# Measurements.net
KiCad netlist of a schematic drawn in Altium Designer
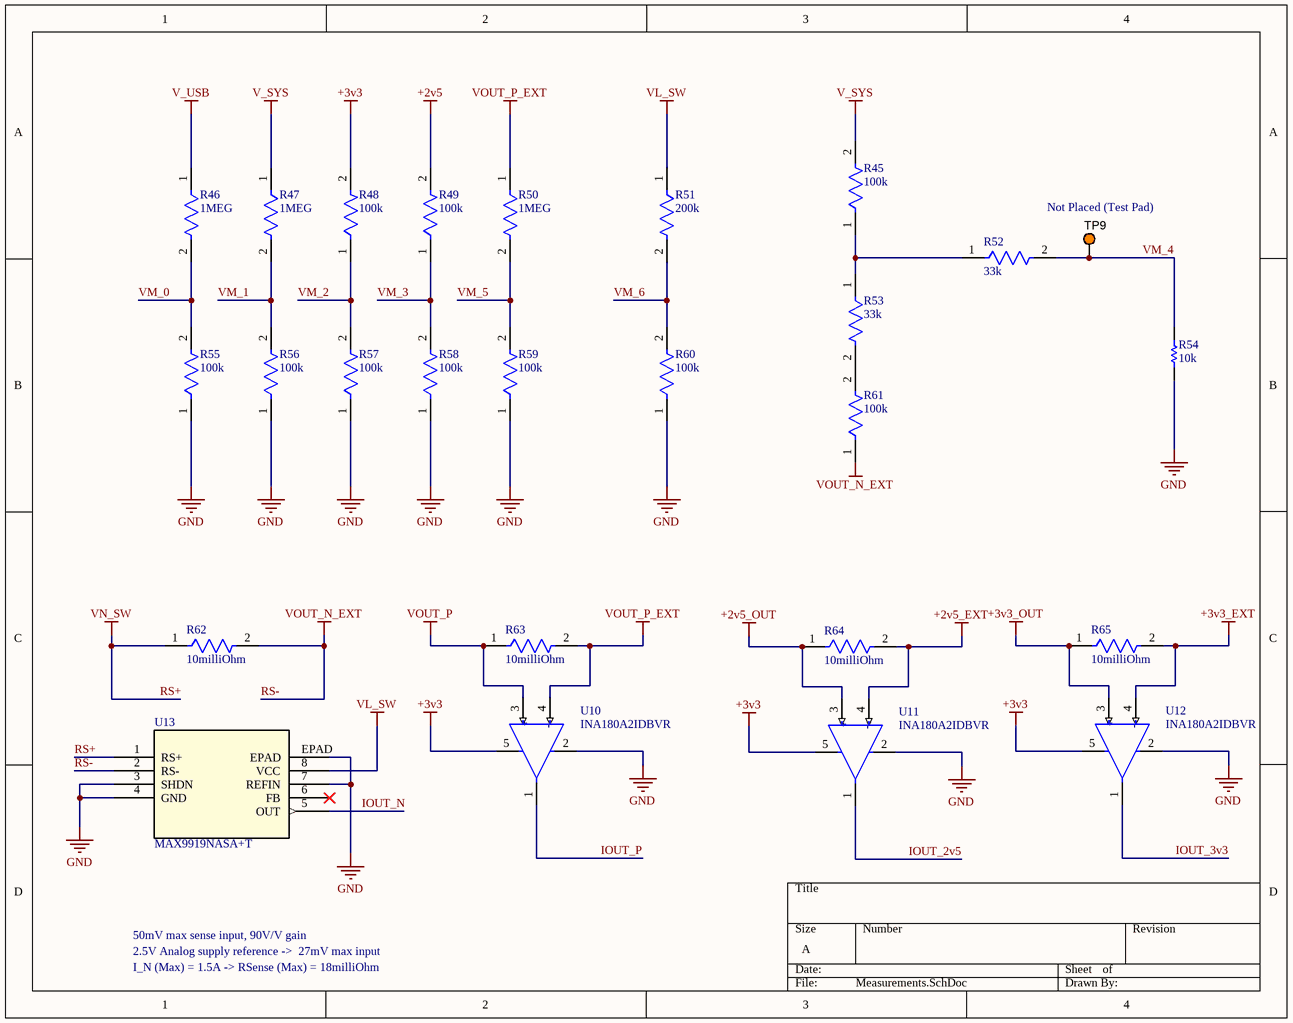
[diagram p0: Measurements.SchDoc]

(export (version "E")
  (design (tool "Eeschema 10.0.6"))
  (components
    (comp (ref "R45")
      (value "100k")
      (footprint "FP-AC0603-IPC_A")
      (description "RES 100kΩ 1.00% 0.2W 0603")
      (libsource (lib "Altium Content Vault") (part "1029c3af85768c4190bb7ad29bc67b5"))
    )
    (comp (ref "R46")
      (value "1MEG")
      (footprint "FP-AC0603-IPC_A")
      (description "RES 1MΩ 1.00% 0.1W 0603")
      (fields (field (name "TOLERANCE") "1%"))
      (libsource (lib "Altium Content Vault") (part "1029c3af85768c4190bb7ad29bc67b5"))
    )
    (comp (ref "R47")
      (value "1MEG")
      (footprint "FP-AC0603-IPC_A")
      (description "RES 1MΩ 1.00% 0.1W 0603")
      (fields (field (name "TOLERANCE") "1%"))
      (libsource (lib "Altium Content Vault") (part "1029c3af85768c4190bb7ad29bc67b5"))
    )
    (comp (ref "R48")
      (value "100k")
      (footprint "FP-AC0603-IPC_A")
      (description "RES 100kΩ 1.00% 0.2W 0603")
      (libsource (lib "Altium Content Vault") (part "1029c3af85768c4190bb7ad29bc67b5"))
    )
    (comp (ref "R49")
      (value "100k")
      (footprint "FP-AC0603-IPC_A")
      (description "RES 100kΩ 1.00% 0.2W 0603")
      (libsource (lib "Altium Content Vault") (part "1029c3af85768c4190bb7ad29bc67b5"))
    )
    (comp (ref "R50")
      (value "1MEG")
      (footprint "FP-AC0603-IPC_A")
      (description "RES 1MΩ 1.00% 0.1W 0603")
      (fields (field (name "TOLERANCE") "1%"))
      (libsource (lib "Altium Content Vault") (part "1029c3af85768c4190bb7ad29bc67b5"))
    )
    (comp (ref "R51")
      (value "200k")
      (footprint "FP-RMCF0603-IPC_A")
      (description "200kΩ ±1% 0.1W 0603 Thick Film Chip Resistor AEC-Q200 compliant")
      (fields (field (name "TOLERANCE") "1%"))
      (libsource (lib "Altium Content Vault") (part "1029c3af85768c4190bb7ad29bc67b5"))
    )
    (comp (ref "R52")
      (value "33k")
      (footprint "FP-CRGCQ0603-IPC_C")
      (description "CRGCQ0603 33KΩ 5% ±100ppm/°C 75V")
      (fields
        (field (name "MANUFACTURER PART NUMBER") "CRGCQ0603J33K")
        (field (name "OCTOPART") "https://octopart.com/crgcq0603j33k-te+connectivity-91018119")
      )
      (libsource (lib "Altium Content Vault") (part "1029c3af85768c4190bb7ad29bc67b5"))
    )
    (comp (ref "R53")
      (value "33k")
      (footprint "FP-CRGCQ0603-IPC_C")
      (description "CRGCQ0603 33KΩ 5% ±100ppm/°C 75V")
      (fields
        (field (name "MANUFACTURER PART NUMBER") "CRGCQ0603J33K")
        (field (name "OCTOPART") "https://octopart.com/crgcq0603j33k-te+connectivity-91018119")
      )
      (libsource (lib "Altium Content Vault") (part "1029c3af85768c4190bb7ad29bc67b5"))
    )
    (comp (ref "R54")
      (value "10k")
      (footprint "RESC1608X55X30NL15T15")
      (fields (field (name "PART NUMBER") "ERJ-3EKF1502V") (field (name "MANUFACTURER") "Panasonic"))
      (libsource (lib "Altium Content Vault") (part "RES"))
    )
    (comp (ref "R55")
      (value "100k")
      (footprint "FP-AC0603-IPC_A")
      (description "RES 100kΩ 1.00% 0.2W 0603")
      (libsource (lib "Altium Content Vault") (part "1029c3af85768c4190bb7ad29bc67b5"))
    )
    (comp (ref "R56")
      (value "100k")
      (footprint "FP-AC0603-IPC_A")
      (description "RES 100kΩ 1.00% 0.2W 0603")
      (libsource (lib "Altium Content Vault") (part "1029c3af85768c4190bb7ad29bc67b5"))
    )
    (comp (ref "R57")
      (value "100k")
      (footprint "FP-AC0603-IPC_A")
      (description "RES 100kΩ 1.00% 0.2W 0603")
      (libsource (lib "Altium Content Vault") (part "1029c3af85768c4190bb7ad29bc67b5"))
    )
    (comp (ref "R58")
      (value "100k")
      (footprint "FP-AC0603-IPC_A")
      (description "RES 100kΩ 1.00% 0.2W 0603")
      (libsource (lib "Altium Content Vault") (part "1029c3af85768c4190bb7ad29bc67b5"))
    )
    (comp (ref "R59")
      (value "100k")
      (footprint "FP-AC0603-IPC_A")
      (description "RES 100kΩ 1.00% 0.2W 0603")
      (libsource (lib "Altium Content Vault") (part "1029c3af85768c4190bb7ad29bc67b5"))
    )
    (comp (ref "R60")
      (value "100k")
      (footprint "FP-AC0603-IPC_A")
      (description "RES 100kΩ 1.00% 0.2W 0603")
      (libsource (lib "Altium Content Vault") (part "1029c3af85768c4190bb7ad29bc67b5"))
    )
    (comp (ref "R61")
      (value "100k")
      (footprint "FP-AC0603-IPC_A")
      (description "RES 100kΩ 1.00% 0.2W 0603")
      (libsource (lib "Altium Content Vault") (part "1029c3af85768c4190bb7ad29bc67b5"))
    )
    (comp (ref "R62")
      (value "10milliOhm")
      (footprint "FP-CSRF0603-high-IPC_A")
      (description "RES 0.01 OHM 1% 1/4W 0603")
      (fields (field (name "TOLERANCE") "1%"))
      (libsource (lib "Altium Content Vault") (part "1029c3af85768c4190bb7ad29bc67b5"))
    )
    (comp (ref "R63")
      (value "10milliOhm")
      (footprint "FP-CSRF0603-high-IPC_A")
      (description "RES 0.01 OHM 1% 1/4W 0603")
      (fields (field (name "TOLERANCE") "1%"))
      (libsource (lib "Altium Content Vault") (part "1029c3af85768c4190bb7ad29bc67b5"))
    )
    (comp (ref "R64")
      (value "10milliOhm")
      (footprint "FP-CSRF0603-high-IPC_A")
      (description "RES 0.01 OHM 1% 1/4W 0603")
      (fields (field (name "TOLERANCE") "1%"))
      (libsource (lib "Altium Content Vault") (part "1029c3af85768c4190bb7ad29bc67b5"))
    )
    (comp (ref "R65")
      (value "10milliOhm")
      (footprint "FP-CSRF0603-high-IPC_A")
      (description "RES 0.01 OHM 1% 1/4W 0603")
      (fields (field (name "TOLERANCE") "1%"))
      (libsource (lib "Altium Content Vault") (part "1029c3af85768c4190bb7ad29bc67b5"))
    )
    (comp (ref "TP9")
      (value "5003")
      (footprint "KSTN-5003")
      (description "Test Point, Orange, 1-Pin THD, RoHS")
      (libsource (lib "Altium Content Vault") (part "TESTPOINT_ORANGE"))
    )
    (comp (ref "U10")
      (value "INA180A2IDBVR")
      (footprint "FP-DBV0005A-MFG")
      (description "IC CURR SENSE 1 CIRCUIT SOT23-5")
      (libsource (lib "Altium Content Vault") (part "0a55cf1a948ad01a3239aec1b7efad0"))
    )
    (comp (ref "U11")
      (value "INA180A2IDBVR")
      (footprint "FP-DBV0005A-MFG")
      (description "IC CURR SENSE 1 CIRCUIT SOT23-5")
      (libsource (lib "Altium Content Vault") (part "0a55cf1a948ad01a3239aec1b7efad0"))
    )
    (comp (ref "U12")
      (value "INA180A2IDBVR")
      (footprint "FP-DBV0005A-MFG")
      (description "IC CURR SENSE 1 CIRCUIT SOT23-5")
      (libsource (lib "Altium Content Vault") (part "0a55cf1a948ad01a3239aec1b7efad0"))
    )
    (comp (ref "U13")
      (value "MAX9919NASA+T")
      (footprint "21-0111D_S8E-14_MXM")
      (description "-20V to +75V Input Range, Precision Uni-/Bidirectional, Current-Sense Amplifiers")
      (fields (field (name "COPYRIGHT") "Copyright (C) 2026 Ultra Librarian. All rights reserved."))
      (libsource (lib "MAX9919NASA&plus_T") (part "MAX9919NASA+T"))
    )
  )
  (nets
    (net (code "1") (name "+2v5") (class "Default")
      (node (ref "R49") (pin "2") (pinfunction "2_2") (pintype "passive"))
    )
    (net (code "2") (name "+2v5_EXT") (class "Default")
      (node (ref "R64") (pin "2") (pinfunction "2_2") (pintype "passive"))
      (node (ref "U11") (pin "4") (pinfunction "IN-_4") (pintype "input"))
    )
    (net (code "3") (name "+2v5_OUT") (class "Default")
      (node (ref "R64") (pin "1") (pinfunction "1_1") (pintype "passive"))
      (node (ref "U11") (pin "3") (pinfunction "IN+_3") (pintype "input"))
    )
    (net (code "4") (name "+3v3") (class "Default")
      (node (ref "R48") (pin "2") (pinfunction "2_2") (pintype "passive"))
      (node (ref "U10") (pin "5") (pinfunction "VS_5") (pintype "power_in"))
      (node (ref "U11") (pin "5") (pinfunction "VS_5") (pintype "power_in"))
      (node (ref "U12") (pin "5") (pinfunction "VS_5") (pintype "power_in"))
    )
    (net (code "5") (name "+3v3_EXT") (class "Default")
      (node (ref "R65") (pin "2") (pinfunction "2_2") (pintype "passive"))
      (node (ref "U12") (pin "4") (pinfunction "IN-_4") (pintype "input"))
    )
    (net (code "6") (name "+3v3_OUT") (class "Default")
      (node (ref "R65") (pin "1") (pinfunction "1_1") (pintype "passive"))
      (node (ref "U12") (pin "3") (pinfunction "IN+_3") (pintype "input"))
    )
    (net (code "7") (name "/IOUT_2v5") (class "Default")
      (node (ref "U11") (pin "1") (pinfunction "OUT_1") (pintype "passive"))
    )
    (net (code "8") (name "/IOUT_3v3") (class "Default")
      (node (ref "U12") (pin "1") (pinfunction "OUT_1") (pintype "passive"))
    )
    (net (code "9") (name "/IOUT_N") (class "Default")
      (node (ref "U13") (pin "5") (pinfunction "OUT_5") (pintype "output"))
    )
    (net (code "10") (name "/IOUT_P") (class "Default")
      (node (ref "U10") (pin "1") (pinfunction "OUT_1") (pintype "passive"))
    )
    (net (code "11") (name "/VM_0") (class "Default")
      (node (ref "R46") (pin "2") (pinfunction "2_2") (pintype "passive"))
      (node (ref "R55") (pin "2") (pinfunction "2_2") (pintype "passive"))
    )
    (net (code "12") (name "/VM_1") (class "Default")
      (node (ref "R47") (pin "2") (pinfunction "2_2") (pintype "passive"))
      (node (ref "R56") (pin "2") (pinfunction "2_2") (pintype "passive"))
    )
    (net (code "13") (name "/VM_2") (class "Default")
      (node (ref "R48") (pin "1") (pinfunction "1_1") (pintype "passive"))
      (node (ref "R57") (pin "2") (pinfunction "2_2") (pintype "passive"))
    )
    (net (code "14") (name "/VM_3") (class "Default")
      (node (ref "R49") (pin "1") (pinfunction "1_1") (pintype "passive"))
      (node (ref "R58") (pin "2") (pinfunction "2_2") (pintype "passive"))
    )
    (net (code "15") (name "/VM_4") (class "Default")
      (node (ref "R52") (pin "2") (pinfunction "2_2") (pintype "passive"))
      (node (ref "R54") (pin "2") (pinfunction "2_2") (pintype "passive"))
      (node (ref "TP9") (pin "1") (pinfunction "1_1") (pintype "passive"))
    )
    (net (code "16") (name "/VM_5") (class "Default")
      (node (ref "R50") (pin "2") (pinfunction "2_2") (pintype "passive"))
      (node (ref "R59") (pin "2") (pinfunction "2_2") (pintype "passive"))
    )
    (net (code "17") (name "/VM_6") (class "Default")
      (node (ref "R51") (pin "2") (pinfunction "2_2") (pintype "passive"))
      (node (ref "R60") (pin "2") (pinfunction "2_2") (pintype "passive"))
    )
    (net (code "18") (name "GND") (class "Default")
      (node (ref "R54") (pin "1") (pinfunction "1_1") (pintype "passive"))
      (node (ref "R55") (pin "1") (pinfunction "1_1") (pintype "passive"))
      (node (ref "R56") (pin "1") (pinfunction "1_1") (pintype "passive"))
      (node (ref "R57") (pin "1") (pinfunction "1_1") (pintype "passive"))
      (node (ref "R58") (pin "1") (pinfunction "1_1") (pintype "passive"))
      (node (ref "R59") (pin "1") (pinfunction "1_1") (pintype "passive"))
      (node (ref "R60") (pin "1") (pinfunction "1_1") (pintype "passive"))
      (node (ref "U10") (pin "2") (pinfunction "GND_2") (pintype "power_in"))
      (node (ref "U11") (pin "2") (pinfunction "GND_2") (pintype "power_in"))
      (node (ref "U12") (pin "2") (pinfunction "GND_2") (pintype "power_in"))
      (node (ref "U13") (pin "3") (pinfunction "SHDN_3") (pintype "passive"))
      (node (ref "U13") (pin "4") (pinfunction "GND_4") (pintype "power_in"))
      (node (ref "U13") (pin "7") (pinfunction "REFIN_7") (pintype "passive"))
      (node (ref "U13") (pin "EPAD") (pinfunction "EPAD_EPAD") (pintype "passive"))
    )
    (net (code "19") (name "Net-(R45-Pad1)") (class "Default")
      (node (ref "R45") (pin "1") (pinfunction "1_1") (pintype "passive"))
      (node (ref "R52") (pin "1") (pinfunction "1_1") (pintype "passive"))
      (node (ref "R53") (pin "1") (pinfunction "1_1") (pintype "passive"))
    )
    (net (code "20") (name "Net-(R53-Pad2)") (class "Default")
      (node (ref "R53") (pin "2") (pinfunction "2_2") (pintype "passive"))
      (node (ref "R61") (pin "2") (pinfunction "2_2") (pintype "passive"))
    )
    (net (code "21") (name "VL_SW") (class "Default")
      (node (ref "R51") (pin "1") (pinfunction "1_1") (pintype "passive"))
      (node (ref "U13") (pin "8") (pinfunction "VCC_8") (pintype "power_in"))
    )
    (net (code "22") (name "VN_SW") (class "Default")
      (node (ref "R62") (pin "1") (pinfunction "1_1") (pintype "passive"))
      (node (ref "U13") (pin "1") (pinfunction "RS+_1") (pintype "passive"))
    )
    (net (code "23") (name "VOUT_N_EXT") (class "Default")
      (node (ref "R61") (pin "1") (pinfunction "1_1") (pintype "passive"))
      (node (ref "R62") (pin "2") (pinfunction "2_2") (pintype "passive"))
      (node (ref "U13") (pin "2") (pinfunction "RS-_2") (pintype "passive"))
    )
    (net (code "24") (name "VOUT_P") (class "Default")
      (node (ref "R63") (pin "1") (pinfunction "1_1") (pintype "passive"))
      (node (ref "U10") (pin "3") (pinfunction "IN+_3") (pintype "input"))
    )
    (net (code "25") (name "VOUT_P_EXT") (class "Default")
      (node (ref "R50") (pin "1") (pinfunction "1_1") (pintype "passive"))
      (node (ref "R63") (pin "2") (pinfunction "2_2") (pintype "passive"))
      (node (ref "U10") (pin "4") (pinfunction "IN-_4") (pintype "input"))
    )
    (net (code "26") (name "V_SYS") (class "Default")
      (node (ref "R45") (pin "2") (pinfunction "2_2") (pintype "passive"))
      (node (ref "R47") (pin "1") (pinfunction "1_1") (pintype "passive"))
    )
    (net (code "27") (name "V_USB") (class "Default")
      (node (ref "R46") (pin "1") (pinfunction "1_1") (pintype "passive"))
    )
    (net (code "28") (name "unconnected-(U13-FB-Pad6)") (class "Default")
      (node (ref "U13") (pin "6") (pinfunction "FB_6") (pintype "passive+no_connect"))
    )
  )
)
